# RX-DESIGN.net
KiCad netlist of a schematic drawn in Altium Designer
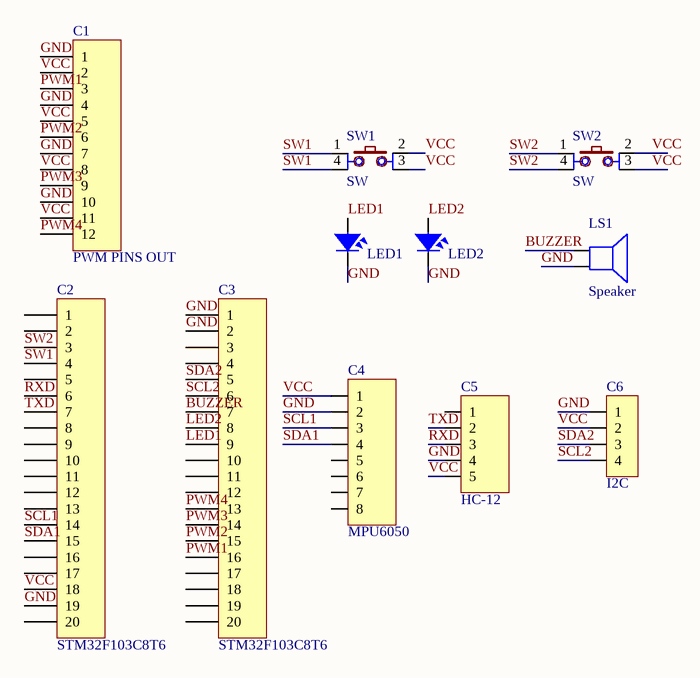
[diagram p0: RX-DESIGN.schdoc]

(export (version "E")
  (design (tool "Eeschema 10.0.6"))
  (components
    (comp (ref "C1")
      (value "PWM PINS OUT")
      (footprint "JP12-D1T")
      (description "WR-PHD 2.54 mm Angled Socket Header")
      (fields
        (field (name "MANUFACTURER") "Würth Elektronik eiSos GmbH")
        (field (name "PARTNO") "613012143121")
        (field (name "CREATED BY") "Karrer Zheng")
      )
      (libsource (lib "LIBRARY") (part "JP12"))
    )
    (comp (ref "C2")
      (value "STM32F103C8T6")
      (footprint "JP20-C1T")
      (description "WR-PHD 2.54 mm Angled Socket Header")
      (fields
        (field (name "MANUFACTURER") "Würth Elektronik eiSos GmbH")
        (field (name "PARTNO") "613020143121")
        (field (name "CREATED BY") "Karrer Zheng")
      )
      (libsource (lib "LIBRARY") (part "JP20"))
    )
    (comp (ref "C3")
      (value "STM32F103C8T6")
      (footprint "JP20-C1T")
      (description "WR-PHD 2.54 mm Angled Socket Header")
      (fields
        (field (name "MANUFACTURER") "Würth Elektronik eiSos GmbH")
        (field (name "PARTNO") "613020143121")
        (field (name "CREATED BY") "Karrer Zheng")
      )
      (libsource (lib "LIBRARY") (part "JP20"))
    )
    (comp (ref "C4")
      (value "MPU6050")
      (footprint "JP8-C1C")
      (description "WR-PHD 2.54 mm Angled Socket Header")
      (fields
        (field (name "MANUFACTURER") "Würth Elektronik eiSos GmbH")
        (field (name "PARTNO") "613008143121")
        (field (name "CREATED BY") "Karrer Zheng")
      )
      (libsource (lib "LIBRARY") (part "JP8"))
    )
    (comp (ref "C5")
      (value "HC-12")
      (footprint "JP5-C1T")
      (description "WR-PHD 2.54 mm Angled Socket Header")
      (fields
        (field (name "MANUFACTURER") "Würth Elektronik eiSos GmbH")
        (field (name "PARTNO") "613005143121")
        (field (name "CREATED BY") "Karrer Zheng")
      )
      (libsource (lib "LIBRARY") (part "JP5"))
    )
    (comp (ref "C6")
      (value "I2C")
      (footprint "JP4-C1T")
      (description "WR-PHD 2.54 mm Angled Socket Header")
      (fields
        (field (name "MANUFACTURER") "Würth Elektronik eiSos GmbH")
        (field (name "PARTNO") "613004143121")
        (field (name "CREATED BY") "Karrer Zheng")
      )
      (libsource (lib "LIBRARY") (part "JP4"))
    )
    (comp (ref "LED1")
      (value "LED")
      (footprint "LED-3MM-YELLOW")
      (description "LED Single colour Green and Red")
      (libsource (lib "LIBRARY") (part "LED"))
    )
    (comp (ref "LED2")
      (value "LED")
      (footprint "LED-3MM-YELLOW")
      (description "LED Single colour Green and Red")
      (libsource (lib "LIBRARY") (part "LED"))
    )
    (comp (ref "LS1")
      (value "Speaker")
      (footprint "SPEAKER")
      (description "Loudspeaker")
      (fields (field (name "PUBLISHER") "Altium Limited"))
      (libsource (lib "LIBRARY") (part "Speaker"))
    )
    (comp (ref "SW1")
      (value "SW")
      (footprint "SW2-DIP")
      (description "Switch button 4 pin")
      (libsource (lib "LIBRARY") (part "SW4"))
    )
    (comp (ref "SW2")
      (value "SW")
      (footprint "SW2-DIP")
      (description "Switch button 4 pin")
      (libsource (lib "LIBRARY") (part "SW4"))
    )
  )
  (nets
    (net (code "1") (name "/BUZZER") (class "Default")
      (node (ref "C3") (pin "7") (pinfunction "7_7") (pintype "passive"))
      (node (ref "LS1") (pin "1") (pinfunction "1_1") (pintype "passive"))
    )
    (net (code "2") (name "/GND") (class "Default")
      (node (ref "C1") (pin "1") (pinfunction "1_1") (pintype "passive"))
      (node (ref "C1") (pin "10") (pinfunction "10_10") (pintype "passive"))
      (node (ref "C1") (pin "4") (pinfunction "4_4") (pintype "passive"))
      (node (ref "C1") (pin "7") (pinfunction "7_7") (pintype "passive"))
      (node (ref "C2") (pin "19") (pinfunction "19_19") (pintype "passive"))
      (node (ref "C3") (pin "1") (pinfunction "1_1") (pintype "passive"))
      (node (ref "C3") (pin "2") (pinfunction "2_2") (pintype "passive"))
      (node (ref "C4") (pin "2") (pinfunction "2_2") (pintype "passive"))
      (node (ref "C5") (pin "4") (pinfunction "4_4") (pintype "passive"))
      (node (ref "C6") (pin "1") (pinfunction "1_1") (pintype "passive"))
      (node (ref "LED1") (pin "2") (pinfunction "2_2") (pintype "passive"))
      (node (ref "LED2") (pin "2") (pinfunction "2_2") (pintype "passive"))
      (node (ref "LS1") (pin "2") (pinfunction "2_2") (pintype "passive"))
    )
    (net (code "3") (name "/LED1") (class "Default")
      (node (ref "C3") (pin "9") (pinfunction "9_9") (pintype "passive"))
      (node (ref "LED1") (pin "1") (pinfunction "1_1") (pintype "passive"))
    )
    (net (code "4") (name "/LED2") (class "Default")
      (node (ref "C3") (pin "8") (pinfunction "8_8") (pintype "passive"))
      (node (ref "LED2") (pin "1") (pinfunction "1_1") (pintype "passive"))
    )
    (net (code "5") (name "/PWM1") (class "Default")
      (node (ref "C1") (pin "3") (pinfunction "3_3") (pintype "passive"))
      (node (ref "C3") (pin "16") (pinfunction "16_16") (pintype "passive"))
    )
    (net (code "6") (name "/PWM2") (class "Default")
      (node (ref "C1") (pin "6") (pinfunction "6_6") (pintype "passive"))
      (node (ref "C3") (pin "15") (pinfunction "15_15") (pintype "passive"))
    )
    (net (code "7") (name "/PWM3") (class "Default")
      (node (ref "C1") (pin "9") (pinfunction "9_9") (pintype "passive"))
      (node (ref "C3") (pin "14") (pinfunction "14_14") (pintype "passive"))
    )
    (net (code "8") (name "/PWM4") (class "Default")
      (node (ref "C1") (pin "12") (pinfunction "12_12") (pintype "passive"))
      (node (ref "C3") (pin "13") (pinfunction "13_13") (pintype "passive"))
    )
    (net (code "9") (name "/RXD") (class "Default")
      (node (ref "C2") (pin "6") (pinfunction "6_6") (pintype "passive"))
      (node (ref "C5") (pin "3") (pinfunction "3_3") (pintype "passive"))
    )
    (net (code "10") (name "/SCL1") (class "Default")
      (node (ref "C2") (pin "14") (pinfunction "14_14") (pintype "passive"))
      (node (ref "C4") (pin "3") (pinfunction "3_3") (pintype "passive"))
    )
    (net (code "11") (name "/SCL2") (class "Default")
      (node (ref "C3") (pin "6") (pinfunction "6_6") (pintype "passive"))
      (node (ref "C6") (pin "4") (pinfunction "4_4") (pintype "passive"))
    )
    (net (code "12") (name "/SDA1") (class "Default")
      (node (ref "C2") (pin "15") (pinfunction "15_15") (pintype "passive"))
      (node (ref "C4") (pin "4") (pinfunction "4_4") (pintype "passive"))
    )
    (net (code "13") (name "/SDA2") (class "Default")
      (node (ref "C3") (pin "5") (pinfunction "5_5") (pintype "passive"))
      (node (ref "C6") (pin "3") (pinfunction "3_3") (pintype "passive"))
    )
    (net (code "14") (name "/SW1") (class "Default")
      (node (ref "C2") (pin "4") (pinfunction "4_4") (pintype "passive"))
      (node (ref "SW1") (pin "1") (pintype "passive"))
      (node (ref "SW1") (pin "4") (pinfunction "4_4") (pintype "passive"))
    )
    (net (code "15") (name "/SW2") (class "Default")
      (node (ref "C2") (pin "3") (pinfunction "3_3") (pintype "passive"))
      (node (ref "SW2") (pin "1") (pintype "passive"))
      (node (ref "SW2") (pin "4") (pinfunction "4_4") (pintype "passive"))
    )
    (net (code "16") (name "/TXD") (class "Default")
      (node (ref "C2") (pin "7") (pinfunction "7_7") (pintype "passive"))
      (node (ref "C5") (pin "2") (pinfunction "2_2") (pintype "passive"))
    )
    (net (code "17") (name "/VCC") (class "Default")
      (node (ref "C1") (pin "11") (pinfunction "11_11") (pintype "passive"))
      (node (ref "C1") (pin "2") (pinfunction "2_2") (pintype "passive"))
      (node (ref "C1") (pin "5") (pinfunction "5_5") (pintype "passive"))
      (node (ref "C1") (pin "8") (pinfunction "8_8") (pintype "passive"))
      (node (ref "C2") (pin "18") (pinfunction "18_18") (pintype "passive"))
      (node (ref "C4") (pin "1") (pinfunction "1_1") (pintype "passive"))
      (node (ref "C5") (pin "5") (pinfunction "5_5") (pintype "passive"))
      (node (ref "C6") (pin "2") (pinfunction "2_2") (pintype "passive"))
      (node (ref "SW1") (pin "2") (pinfunction "2_2") (pintype "passive"))
      (node (ref "SW1") (pin "3") (pinfunction "3_3") (pintype "passive"))
      (node (ref "SW2") (pin "2") (pinfunction "2_2") (pintype "passive"))
      (node (ref "SW2") (pin "3") (pinfunction "3_3") (pintype "passive"))
    )
    (net (code "18") (name "unconnected-(C2-Pad1)") (class "Default")
      (node (ref "C2") (pin "1") (pinfunction "1_1") (pintype "passive"))
    )
    (net (code "19") (name "unconnected-(C2-Pad2)") (class "Default")
      (node (ref "C2") (pin "2") (pinfunction "2_2") (pintype "passive"))
    )
    (net (code "20") (name "unconnected-(C2-Pad5)") (class "Default")
      (node (ref "C2") (pin "5") (pinfunction "5_5") (pintype "passive"))
    )
    (net (code "21") (name "unconnected-(C2-Pad8)") (class "Default")
      (node (ref "C2") (pin "8") (pinfunction "8_8") (pintype "passive"))
    )
    (net (code "22") (name "unconnected-(C2-Pad9)") (class "Default")
      (node (ref "C2") (pin "9") (pinfunction "9_9") (pintype "passive"))
    )
    (net (code "23") (name "unconnected-(C2-Pad10)") (class "Default")
      (node (ref "C2") (pin "10") (pinfunction "10_10") (pintype "passive"))
    )
    (net (code "24") (name "unconnected-(C2-Pad11)") (class "Default")
      (node (ref "C2") (pin "11") (pinfunction "11_11") (pintype "passive"))
    )
    (net (code "25") (name "unconnected-(C2-Pad12)") (class "Default")
      (node (ref "C2") (pin "12") (pinfunction "12_12") (pintype "passive"))
    )
    (net (code "26") (name "unconnected-(C2-Pad13)") (class "Default")
      (node (ref "C2") (pin "13") (pinfunction "13_13") (pintype "passive"))
    )
    (net (code "27") (name "unconnected-(C2-Pad16)") (class "Default")
      (node (ref "C2") (pin "16") (pinfunction "16_16") (pintype "passive"))
    )
    (net (code "28") (name "unconnected-(C2-Pad17)") (class "Default")
      (node (ref "C2") (pin "17") (pinfunction "17_17") (pintype "passive"))
    )
    (net (code "29") (name "unconnected-(C2-Pad20)") (class "Default")
      (node (ref "C2") (pin "20") (pinfunction "20_20") (pintype "passive"))
    )
    (net (code "30") (name "unconnected-(C3-Pad3)") (class "Default")
      (node (ref "C3") (pin "3") (pinfunction "3_3") (pintype "passive"))
    )
    (net (code "31") (name "unconnected-(C3-Pad4)") (class "Default")
      (node (ref "C3") (pin "4") (pinfunction "4_4") (pintype "passive"))
    )
    (net (code "32") (name "unconnected-(C3-Pad10)") (class "Default")
      (node (ref "C3") (pin "10") (pinfunction "10_10") (pintype "passive"))
    )
    (net (code "33") (name "unconnected-(C3-Pad11)") (class "Default")
      (node (ref "C3") (pin "11") (pinfunction "11_11") (pintype "passive"))
    )
    (net (code "34") (name "unconnected-(C3-Pad12)") (class "Default")
      (node (ref "C3") (pin "12") (pinfunction "12_12") (pintype "passive"))
    )
    (net (code "35") (name "unconnected-(C3-Pad17)") (class "Default")
      (node (ref "C3") (pin "17") (pinfunction "17_17") (pintype "passive"))
    )
    (net (code "36") (name "unconnected-(C3-Pad18)") (class "Default")
      (node (ref "C3") (pin "18") (pinfunction "18_18") (pintype "passive"))
    )
    (net (code "37") (name "unconnected-(C3-Pad19)") (class "Default")
      (node (ref "C3") (pin "19") (pinfunction "19_19") (pintype "passive"))
    )
    (net (code "38") (name "unconnected-(C3-Pad20)") (class "Default")
      (node (ref "C3") (pin "20") (pinfunction "20_20") (pintype "passive"))
    )
    (net (code "39") (name "unconnected-(C4-Pad5)") (class "Default")
      (node (ref "C4") (pin "5") (pinfunction "5_5") (pintype "passive"))
    )
    (net (code "40") (name "unconnected-(C4-Pad6)") (class "Default")
      (node (ref "C4") (pin "6") (pinfunction "6_6") (pintype "passive"))
    )
    (net (code "41") (name "unconnected-(C4-Pad7)") (class "Default")
      (node (ref "C4") (pin "7") (pinfunction "7_7") (pintype "passive"))
    )
    (net (code "42") (name "unconnected-(C4-Pad8)") (class "Default")
      (node (ref "C4") (pin "8") (pinfunction "8_8") (pintype "passive"))
    )
    (net (code "43") (name "unconnected-(C5-Pad1)") (class "Default")
      (node (ref "C5") (pin "1") (pinfunction "1_1") (pintype "passive"))
    )
  )
)
